# RC_RX_CABELL_V3_FHSS.net
KiCad netlist of a schematic drawn in EAGLE
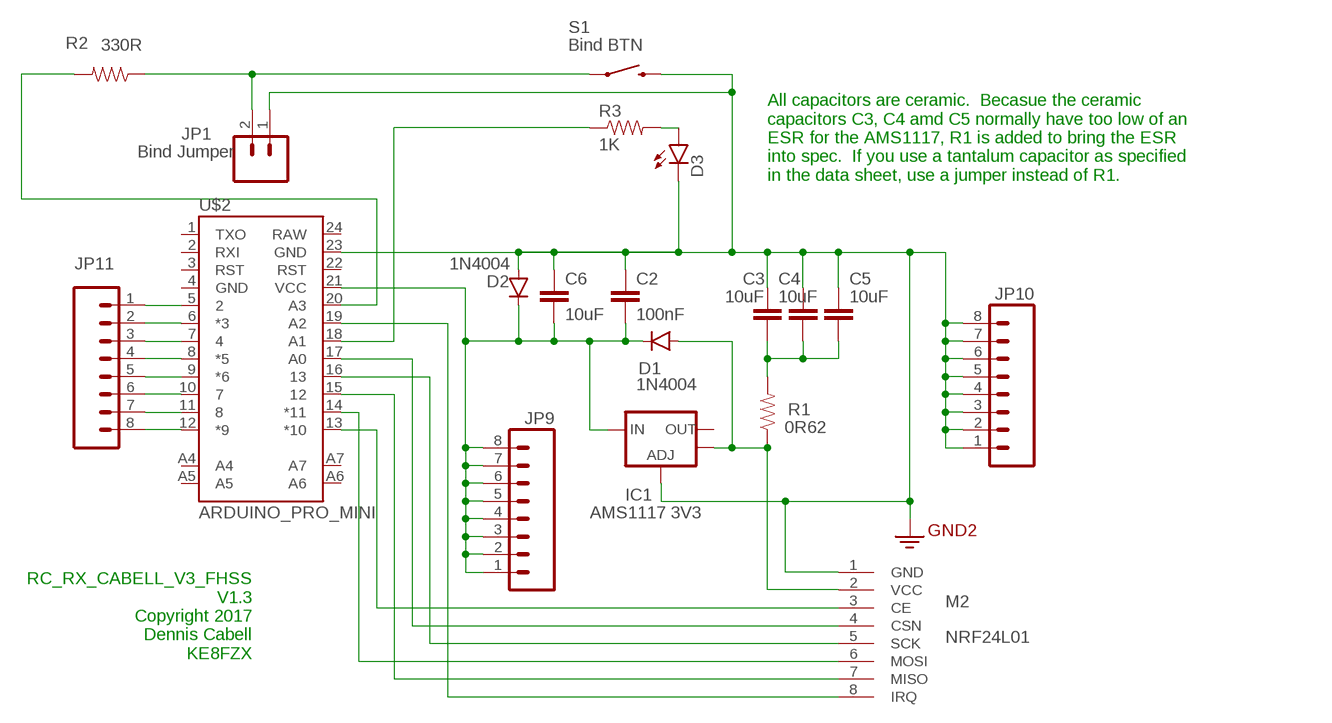
[diagram p0: schematic, sheet 1]

(export (version "E")
  (design (tool "Eeschema 10.0.6"))
  (components
    (comp (ref "C2")
      (value "100nF")
      (footprint "eagle-import:CAP-PTH-5MM")
      (libsource (lib "eagle-import") (part "CAPPTH1"))
    )
    (comp (ref "C3")
      (value "10uF")
      (footprint "eagle-import:CAP-PTH-5MM")
      (libsource (lib "eagle-import") (part "CAPPTH1"))
    )
    (comp (ref "C4")
      (value "10uF")
      (footprint "eagle-import:CAP-PTH-5MM")
      (libsource (lib "eagle-import") (part "CAPPTH1"))
    )
    (comp (ref "C5")
      (value "10uF")
      (footprint "eagle-import:CAP-PTH-5MM")
      (libsource (lib "eagle-import") (part "CAPPTH1"))
    )
    (comp (ref "C6")
      (value "10uF")
      (footprint "eagle-import:CAP-PTH-5MM")
      (libsource (lib "eagle-import") (part "CAPPTH1"))
    )
    (comp (ref "D1")
      (value "1N4004")
      (footprint "eagle-import:DIODE-1N4001")
      (libsource (lib "eagle-import") (part "DIODEPTH"))
    )
    (comp (ref "D2")
      (value "1N4004")
      (footprint "eagle-import:DIODE-1N4001")
      (libsource (lib "eagle-import") (part "DIODEPTH"))
    )
    (comp (ref "D3")
      (value "LED3MM")
      (footprint "eagle-import:LED3MM")
      (libsource (lib "eagle-import") (part "LED3MM"))
    )
    (comp (ref "IC1")
      (value "AMS1117 3V3")
      (footprint "eagle-import:SOT223")
      (libsource (lib "eagle-import") (part "V_REG_LM1117SOT223"))
    )
    (comp (ref "JP1")
      (value "Bind Jumper")
      (footprint "eagle-import:1X02")
      (libsource (lib "eagle-import") (part "M02PTH"))
    )
    (comp (ref "JP9")
      (value "M08")
      (footprint "eagle-import:1X08_ROUND")
      (libsource (lib "eagle-import") (part "M08"))
    )
    (comp (ref "JP10")
      (value "M08")
      (footprint "eagle-import:1X08_ROUND")
      (libsource (lib "eagle-import") (part "M08"))
    )
    (comp (ref "JP11")
      (value "M08")
      (footprint "eagle-import:1X08_ROUND")
      (libsource (lib "eagle-import") (part "M08"))
    )
    (comp (ref "M2")
      (value "NRF24L01")
      (footprint "eagle-import:WIRELESS-NRF24L01")
      (libsource (lib "eagle-import") (part "WIRELESS-NRF24L01"))
    )
    (comp (ref "R1")
      (value "0R62")
      (footprint "eagle-import:AXIAL-0.5")
      (libsource (lib "eagle-import") (part "RESISTORPTH-1/2W"))
    )
    (comp (ref "R2")
      (value "330R")
      (footprint "eagle-import:AXIAL-0.3")
      (libsource (lib "eagle-import") (part "RESISTORAXIAL-0.3"))
    )
    (comp (ref "R3")
      (value "1K")
      (footprint "eagle-import:AXIAL-0.3")
      (libsource (lib "eagle-import") (part "RESISTORAXIAL-0.3"))
    )
    (comp (ref "S1")
      (value "Bind BTN")
      (footprint "eagle-import:TACTILE-SWITCH-1101NE")
      (libsource (lib "eagle-import") (part "SWITCH-MOMENTARY-2SMD-1101NE"))
    )
    (comp (ref "U$2")
      (value "ARDUINO_PRO_MINI")
      (footprint "eagle-import:ARDUINO_PRO_MINI")
      (libsource (lib "eagle-import") (part "ARDUINO_PRO_MINI"))
    )
  )
  (nets
    (net (code "1") (name "GND2") (class "Default")
      (node (ref "C2") (pin "1") (pinfunction "1_1") (pintype "passive"))
      (node (ref "C3") (pin "1") (pinfunction "1_1") (pintype "passive"))
      (node (ref "C4") (pin "1") (pinfunction "1_1") (pintype "passive"))
      (node (ref "C5") (pin "1") (pinfunction "1_1") (pintype "passive"))
      (node (ref "C6") (pin "1") (pinfunction "1_1") (pintype "passive"))
      (node (ref "D2") (pin "A") (pinfunction "A_A") (pintype "passive"))
      (node (ref "D3") (pin "K") (pinfunction "C_K") (pintype "passive"))
      (node (ref "IC1") (pin "1") (pinfunction "ADJ_1") (pintype "input"))
      (node (ref "JP1") (pin "1") (pinfunction "1_1") (pintype "passive"))
      (node (ref "JP10") (pin "1") (pinfunction "1_1") (pintype "passive"))
      (node (ref "JP10") (pin "2") (pinfunction "2_2") (pintype "passive"))
      (node (ref "JP10") (pin "3") (pinfunction "3_3") (pintype "passive"))
      (node (ref "JP10") (pin "4") (pinfunction "4_4") (pintype "passive"))
      (node (ref "JP10") (pin "5") (pinfunction "5_5") (pintype "passive"))
      (node (ref "JP10") (pin "6") (pinfunction "6_6") (pintype "passive"))
      (node (ref "JP10") (pin "7") (pinfunction "7_7") (pintype "passive"))
      (node (ref "JP10") (pin "8") (pinfunction "8_8") (pintype "passive"))
      (node (ref "M2") (pin "1") (pinfunction "GND_1") (pintype "power_in"))
      (node (ref "S1") (pin "2") (pinfunction "2_2") (pintype "passive"))
      (node (ref "U$2") (pin "23") (pinfunction "GND_23") (pintype "bidirectional"))
    )
    (net (code "2") (name "Net-(IC1-IN)") (class "Default")
      (node (ref "C2") (pin "2") (pinfunction "2_2") (pintype "passive"))
      (node (ref "C6") (pin "2") (pinfunction "2_2") (pintype "passive"))
      (node (ref "D1") (pin "C") (pinfunction "C_C") (pintype "passive"))
      (node (ref "D2") (pin "C") (pinfunction "C_C") (pintype "passive"))
      (node (ref "IC1") (pin "3") (pinfunction "IN_3") (pintype "input"))
      (node (ref "JP9") (pin "1") (pinfunction "1_1") (pintype "passive"))
      (node (ref "JP9") (pin "2") (pinfunction "2_2") (pintype "passive"))
      (node (ref "JP9") (pin "3") (pinfunction "3_3") (pintype "passive"))
      (node (ref "JP9") (pin "4") (pinfunction "4_4") (pintype "passive"))
      (node (ref "JP9") (pin "5") (pinfunction "5_5") (pintype "passive"))
      (node (ref "JP9") (pin "6") (pinfunction "6_6") (pintype "passive"))
      (node (ref "JP9") (pin "7") (pinfunction "7_7") (pintype "passive"))
      (node (ref "JP9") (pin "8") (pinfunction "8_8") (pintype "passive"))
      (node (ref "U$2") (pin "21") (pinfunction "VCC_21") (pintype "bidirectional"))
    )
    (net (code "3") (name "Net-(M2-CE)") (class "Default")
      (node (ref "M2") (pin "3") (pinfunction "CE_3") (pintype "bidirectional"))
      (node (ref "U$2") (pin "13") (pinfunction "*10_13") (pintype "bidirectional"))
    )
    (net (code "4") (name "Net-(M2-CSN)") (class "Default")
      (node (ref "M2") (pin "4") (pinfunction "CSN_4") (pintype "bidirectional"))
      (node (ref "U$2") (pin "17") (pinfunction "A0_17") (pintype "bidirectional"))
    )
    (net (code "5") (name "Net-(M2-IRQ)") (class "Default")
      (node (ref "M2") (pin "8") (pinfunction "IRQ_8") (pintype "bidirectional"))
      (node (ref "U$2") (pin "19") (pinfunction "A2_19") (pintype "bidirectional"))
    )
    (net (code "6") (name "Net-(M2-MISO)") (class "Default")
      (node (ref "M2") (pin "7") (pinfunction "MISO_7") (pintype "bidirectional"))
      (node (ref "U$2") (pin "15") (pinfunction "12_15") (pintype "bidirectional"))
    )
    (net (code "7") (name "Net-(M2-MOSI)") (class "Default")
      (node (ref "M2") (pin "6") (pinfunction "MOSI_6") (pintype "bidirectional"))
      (node (ref "U$2") (pin "14") (pinfunction "*11_14") (pintype "bidirectional"))
    )
    (net (code "8") (name "Net-(M2-SCK)") (class "Default")
      (node (ref "M2") (pin "5") (pinfunction "SCK_5") (pintype "bidirectional"))
      (node (ref "U$2") (pin "16") (pinfunction "13_16") (pintype "bidirectional"))
    )
    (net (code "9") (name "Net-(M2-VCC)") (class "Default")
      (node (ref "D1") (pin "A") (pinfunction "A_A") (pintype "passive"))
      (node (ref "IC1") (pin "4") (pinfunction "OUT_4") (pintype "output"))
      (node (ref "M2") (pin "2") (pinfunction "VCC_2") (pintype "power_in"))
      (node (ref "R1") (pin "P$1") (pinfunction "1_P$1") (pintype "passive"))
    )
    (net (code "10") (name "Net-(R1-2)") (class "Default")
      (node (ref "C3") (pin "2") (pinfunction "2_2") (pintype "passive"))
      (node (ref "C4") (pin "2") (pinfunction "2_2") (pintype "passive"))
      (node (ref "C5") (pin "2") (pinfunction "2_2") (pintype "passive"))
      (node (ref "R1") (pin "P$2") (pinfunction "2_P$2") (pintype "passive"))
    )
    (net (code "11") (name "Net-(R2-1)") (class "Default")
      (node (ref "JP1") (pin "2") (pinfunction "2_2") (pintype "passive"))
      (node (ref "R2") (pin "P$1") (pinfunction "1_P$1") (pintype "passive"))
      (node (ref "S1") (pin "1") (pinfunction "1_1") (pintype "passive"))
    )
    (net (code "12") (name "Net-(R2-2)") (class "Default")
      (node (ref "R2") (pin "P$2") (pinfunction "2_P$2") (pintype "passive"))
      (node (ref "U$2") (pin "20") (pinfunction "A3_20") (pintype "bidirectional"))
    )
    (net (code "13") (name "Net-(R3-1)") (class "Default")
      (node (ref "R3") (pin "P$1") (pinfunction "1_P$1") (pintype "passive"))
      (node (ref "U$2") (pin "18") (pinfunction "A1_18") (pintype "bidirectional"))
    )
    (net (code "14") (name "Net-(R3-2)") (class "Default")
      (node (ref "D3") (pin "A") (pinfunction "A_A") (pintype "passive"))
      (node (ref "R3") (pin "P$2") (pinfunction "2_P$2") (pintype "passive"))
    )
    (net (code "15") (name "Net-(U$2-*3)") (class "Default")
      (node (ref "JP11") (pin "2") (pinfunction "2_2") (pintype "passive"))
      (node (ref "U$2") (pin "6") (pinfunction "*3_6") (pintype "bidirectional"))
    )
    (net (code "16") (name "Net-(U$2-*5)") (class "Default")
      (node (ref "JP11") (pin "4") (pinfunction "4_4") (pintype "passive"))
      (node (ref "U$2") (pin "8") (pinfunction "*5_8") (pintype "bidirectional"))
    )
    (net (code "17") (name "Net-(U$2-*6)") (class "Default")
      (node (ref "JP11") (pin "5") (pinfunction "5_5") (pintype "passive"))
      (node (ref "U$2") (pin "9") (pinfunction "*6_9") (pintype "bidirectional"))
    )
    (net (code "18") (name "Net-(U$2-*9)") (class "Default")
      (node (ref "JP11") (pin "8") (pinfunction "8_8") (pintype "passive"))
      (node (ref "U$2") (pin "12") (pinfunction "*9_12") (pintype "bidirectional"))
    )
    (net (code "19") (name "Net-(U$2-2)") (class "Default")
      (node (ref "JP11") (pin "1") (pinfunction "1_1") (pintype "passive"))
      (node (ref "U$2") (pin "5") (pinfunction "2_5") (pintype "bidirectional"))
    )
    (net (code "20") (name "Net-(U$2-4)") (class "Default")
      (node (ref "JP11") (pin "3") (pinfunction "3_3") (pintype "passive"))
      (node (ref "U$2") (pin "7") (pinfunction "4_7") (pintype "bidirectional"))
    )
    (net (code "21") (name "Net-(U$2-7)") (class "Default")
      (node (ref "JP11") (pin "6") (pinfunction "6_6") (pintype "passive"))
      (node (ref "U$2") (pin "10") (pinfunction "7_10") (pintype "bidirectional"))
    )
    (net (code "22") (name "Net-(U$2-8)") (class "Default")
      (node (ref "JP11") (pin "7") (pinfunction "7_7") (pintype "passive"))
      (node (ref "U$2") (pin "11") (pinfunction "8_11") (pintype "bidirectional"))
    )
    (net (code "23") (name "unconnected-(IC1-OUT-Pad2)") (class "Default")
      (node (ref "IC1") (pin "2") (pinfunction "OUT_2") (pintype "output"))
    )
    (net (code "24") (name "unconnected-(U$2-GND-Pad4)") (class "Default")
      (node (ref "U$2") (pin "4") (pinfunction "GND_4") (pintype "bidirectional"))
    )
    (net (code "25") (name "unconnected-(U$2-PadA4)") (class "Default")
      (node (ref "U$2") (pin "A4") (pinfunction "A4_A4") (pintype "bidirectional"))
    )
    (net (code "26") (name "unconnected-(U$2-PadA5)") (class "Default")
      (node (ref "U$2") (pin "A5") (pinfunction "A5_A5") (pintype "bidirectional"))
    )
    (net (code "27") (name "unconnected-(U$2-PadA6)") (class "Default")
      (node (ref "U$2") (pin "A6") (pinfunction "A6_A6") (pintype "bidirectional"))
    )
    (net (code "28") (name "unconnected-(U$2-PadA7)") (class "Default")
      (node (ref "U$2") (pin "A7") (pinfunction "A7_A7") (pintype "bidirectional"))
    )
    (net (code "29") (name "unconnected-(U$2-RAW-Pad24)") (class "Default")
      (node (ref "U$2") (pin "24") (pinfunction "RAW_24") (pintype "bidirectional"))
    )
    (net (code "30") (name "unconnected-(U$2-RST-Pad3)") (class "Default")
      (node (ref "U$2") (pin "3") (pinfunction "RST_3") (pintype "bidirectional"))
    )
    (net (code "31") (name "unconnected-(U$2-RST-Pad22)") (class "Default")
      (node (ref "U$2") (pin "22") (pinfunction "RST_22") (pintype "bidirectional"))
    )
    (net (code "32") (name "unconnected-(U$2-RXI-Pad2)") (class "Default")
      (node (ref "U$2") (pin "2") (pinfunction "RXI_2") (pintype "bidirectional"))
    )
    (net (code "33") (name "unconnected-(U$2-TXO-Pad1)") (class "Default")
      (node (ref "U$2") (pin "1") (pinfunction "TXO_1") (pintype "bidirectional"))
    )
  )
)
